# heater.net
KiCad netlist of a schematic drawn in EAGLE
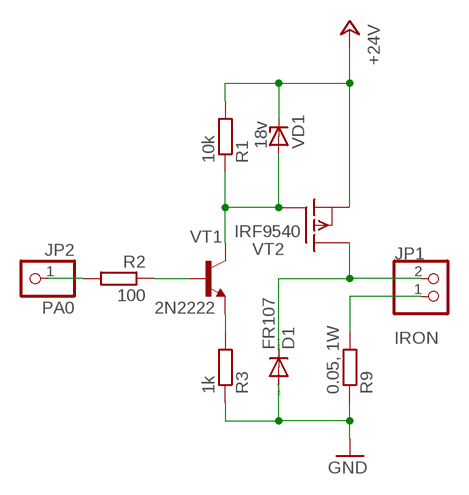
[diagram p0: schematic, sheet 1]

(export (version "E")
  (design (tool "Eeschema 10.0.6"))
  (components
    (comp (ref "D1")
      (value "FR107")
      (footprint "eagle-import:DO41-10")
      (libsource (lib "eagle-import") (part "1N4004"))
    )
    (comp (ref "JP1")
      (value "IRON")
      (footprint "eagle-import:1X02")
      (libsource (lib "eagle-import") (part "PINHD-1X2"))
    )
    (comp (ref "JP2")
      (value "PA0")
      (footprint "eagle-import:1X01")
      (libsource (lib "eagle-import") (part "PINHD-1X1"))
    )
    (comp (ref "R1")
      (value "10k")
      (footprint "eagle-import:0207_10")
      (libsource (lib "eagle-import") (part "R-EU_0207/10"))
    )
    (comp (ref "R2")
      (value "100")
      (footprint "eagle-import:0207_10")
      (libsource (lib "eagle-import") (part "R-EU_0207/10"))
    )
    (comp (ref "R3")
      (value "1k")
      (footprint "eagle-import:0207_10")
      (libsource (lib "eagle-import") (part "R-EU_0207/10"))
    )
    (comp (ref "R9")
      (value "0.05, 1W")
      (footprint "eagle-import:0207_10")
      (libsource (lib "eagle-import") (part "R-EU_0207/10"))
    )
    (comp (ref "VD1")
      (value "18v")
      (footprint "eagle-import:C1702-15")
      (libsource (lib "eagle-import") (part "ZENER-DIODEC1702-15"))
    )
    (comp (ref "VT1")
      (value "2N2222")
      (footprint "eagle-import:TO18")
      (libsource (lib "eagle-import") (part "2N2222"))
    )
    (comp (ref "VT2")
      (value "IRF9540")
      (footprint "eagle-import:TO220")
      (libsource (lib "eagle-import") (part "IRF9530"))
    )
  )
  (nets
    (net (code "1") (name "+24V") (class "Default")
      (node (ref "R1") (pin "2") (pinfunction "2_2") (pintype "passive"))
      (node (ref "VD1") (pin "C") (pinfunction "C_C") (pintype "passive"))
      (node (ref "VT2") (pin "3") (pinfunction "S_3") (pintype "passive"))
    )
    (net (code "2") (name "GND") (class "Default")
      (node (ref "D1") (pin "A") (pinfunction "A_A") (pintype "passive"))
      (node (ref "R3") (pin "1") (pinfunction "1_1") (pintype "passive"))
      (node (ref "R9") (pin "1") (pinfunction "1_1") (pintype "passive"))
    )
    (net (code "3") (name "Net-(JP1-Pad1)") (class "Default")
      (node (ref "JP1") (pin "1") (pinfunction "1_1") (pintype "passive"))
      (node (ref "R9") (pin "2") (pinfunction "2_2") (pintype "passive"))
    )
    (net (code "4") (name "Net-(JP2-Pad1)") (class "Default")
      (node (ref "JP2") (pin "1") (pinfunction "1_1") (pintype "passive"))
      (node (ref "R2") (pin "2") (pinfunction "2_2") (pintype "passive"))
    )
    (net (code "5") (name "Net-(VT1-B)") (class "Default")
      (node (ref "R2") (pin "1") (pinfunction "1_1") (pintype "passive"))
      (node (ref "VT1") (pin "2") (pinfunction "B_2") (pintype "passive"))
    )
    (net (code "6") (name "Net-(VT1-C)") (class "Default")
      (node (ref "R1") (pin "1") (pinfunction "1_1") (pintype "passive"))
      (node (ref "VD1") (pin "A") (pinfunction "A_A") (pintype "passive"))
      (node (ref "VT1") (pin "3") (pinfunction "C_3") (pintype "passive"))
      (node (ref "VT2") (pin "1") (pinfunction "G_1") (pintype "passive"))
    )
    (net (code "7") (name "Net-(VT1-E)") (class "Default")
      (node (ref "R3") (pin "2") (pinfunction "2_2") (pintype "passive"))
      (node (ref "VT1") (pin "1") (pinfunction "E_1") (pintype "passive"))
    )
    (net (code "8") (name "Net-(VT2-D)") (class "Default")
      (node (ref "D1") (pin "C") (pinfunction "C_C") (pintype "passive"))
      (node (ref "JP1") (pin "2") (pinfunction "2_2") (pintype "passive"))
      (node (ref "VT2") (pin "2") (pinfunction "D_2") (pintype "passive"))
    )
  )
)
